# PLWD_Bluetooth.net
KiCad netlist of a schematic drawn in Altium Designer
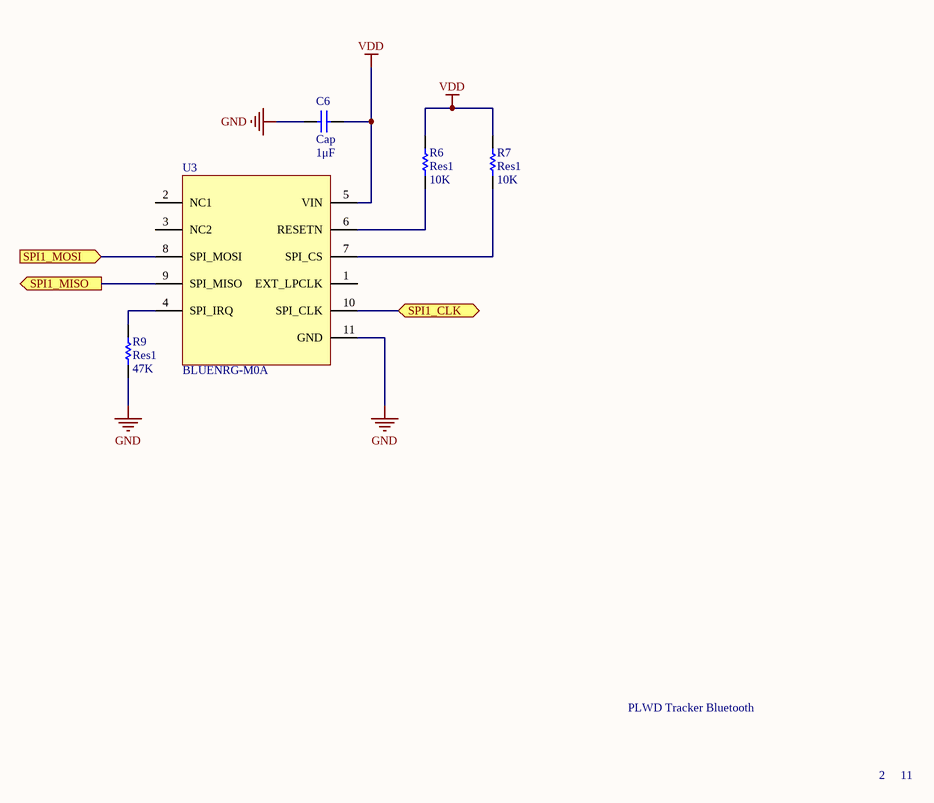
[diagram p0: PLWD_Bluetooth.SchDoc]

(export (version "E")
  (design (tool "Eeschema 10.0.6"))
  (components
    (comp (ref "C6")
      (value "Cap")
      (footprint "RAD-0.3")
      (description "Capacitor")
      (fields (field (name "ALTIUM_VALUE") "1μF") (field (name "PUBLISHER") "Altium Limited"))
      (libsource (lib "Miscellaneous Devices") (part "Cap"))
    )
    (comp (ref "R6")
      (value "Res1")
      (footprint "AXIAL-0.3")
      (description "Resistor")
      (fields (field (name "ALTIUM_VALUE") "10K") (field (name "PUBLISHER") "Altium Limited"))
      (libsource (lib "Miscellaneous Devices") (part "Res1"))
    )
    (comp (ref "R7")
      (value "Res1")
      (footprint "AXIAL-0.3")
      (description "Resistor")
      (fields (field (name "ALTIUM_VALUE") "10K") (field (name "PUBLISHER") "Altium Limited"))
      (libsource (lib "Miscellaneous Devices") (part "Res1"))
    )
    (comp (ref "R9")
      (value "Res1")
      (footprint "AXIAL-0.3")
      (description "Resistor")
      (fields (field (name "ALTIUM_VALUE") "47K") (field (name "PUBLISHER") "Altium Limited"))
      (libsource (lib "Miscellaneous Devices") (part "Res1"))
    )
    (comp (ref "U3")
      (value "BLUENRG-M0A")
      (description "Very low power network processor module for Bluetooth® low energy v4.2")
      (fields (field (name "MANUFACTURER") "STMicroelectronics"))
      (libsource (lib "PLWD_PartLib") (part "BLUENRG-M0A"))
    )
  )
  (nets
    (net (code "1") (name "/SPI1_CLK") (class "Default")
      (node (ref "U3") (pin "10") (pinfunction "SPI_CLK_10") (pintype "passive"))
    )
    (net (code "2") (name "/SPI1_MISO") (class "Default")
      (node (ref "U3") (pin "9") (pinfunction "SPI_MISO_9") (pintype "passive"))
    )
    (net (code "3") (name "/SPI1_MOSI") (class "Default")
      (node (ref "U3") (pin "8") (pinfunction "SPI_MOSI_8") (pintype "passive"))
    )
    (net (code "4") (name "GND") (class "Default")
      (node (ref "C6") (pin "1") (pinfunction "1_1") (pintype "passive"))
      (node (ref "R9") (pin "1") (pinfunction "1_1") (pintype "passive"))
      (node (ref "U3") (pin "11") (pinfunction "GND_11") (pintype "passive"))
    )
    (net (code "5") (name "Net-(U3-RESETN)") (class "Default")
      (node (ref "R6") (pin "1") (pinfunction "1_1") (pintype "passive"))
      (node (ref "U3") (pin "6") (pinfunction "RESETN_6") (pintype "passive"))
    )
    (net (code "6") (name "Net-(U3-SPI_CS)") (class "Default")
      (node (ref "R7") (pin "1") (pinfunction "1_1") (pintype "passive"))
      (node (ref "U3") (pin "7") (pinfunction "SPI_CS_7") (pintype "passive"))
    )
    (net (code "7") (name "Net-(U3-SPI_IRQ)") (class "Default")
      (node (ref "R9") (pin "2") (pinfunction "2_2") (pintype "passive"))
      (node (ref "U3") (pin "4") (pinfunction "SPI_IRQ_4") (pintype "passive"))
    )
    (net (code "8") (name "VDD") (class "Default")
      (node (ref "C6") (pin "2") (pinfunction "2_2") (pintype "passive"))
      (node (ref "R6") (pin "2") (pinfunction "2_2") (pintype "passive"))
      (node (ref "R7") (pin "2") (pinfunction "2_2") (pintype "passive"))
      (node (ref "U3") (pin "5") (pinfunction "VIN_5") (pintype "passive"))
    )
    (net (code "9") (name "unconnected-(U3-EXT_LPCLK-Pad1)") (class "Default")
      (node (ref "U3") (pin "1") (pinfunction "EXT_LPCLK_1") (pintype "passive"))
    )
    (net (code "10") (name "unconnected-(U3-NC1-Pad2)") (class "Default")
      (node (ref "U3") (pin "2") (pinfunction "NC1_2") (pintype "passive"))
    )
    (net (code "11") (name "unconnected-(U3-NC2-Pad3)") (class "Default")
      (node (ref "U3") (pin "3") (pinfunction "NC2_3") (pintype "passive"))
    )
  )
)
